# BMS-S09-V00-TemperatureSensors.net
KiCad netlist of a schematic drawn in Altium Designer
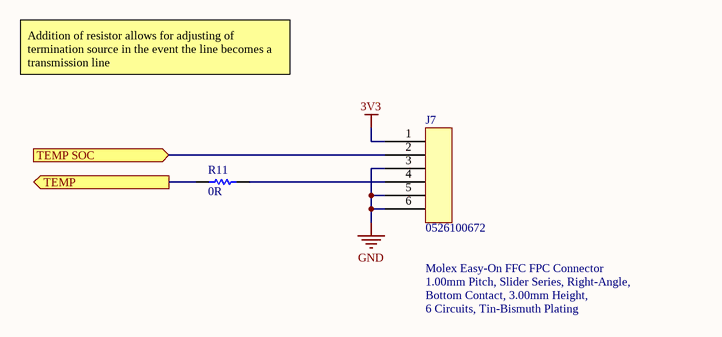
[diagram p0: BMS-S09-V00-TemperatureSensors.SchDoc]

(export (version "E")
  (design (tool "Eeschema 10.0.6"))
  (components
    (comp (ref "J7")
      (value "0526100672")
      (footprint "526100672")
      (libsource (lib "FFCConnectors") (part "6PinMOLEX"))
    )
    (comp (ref "R11")
      (value "0R")
      (footprint "Res_ThinFilm_0603")
      (description "Resistor, SMD, 0R, 0.1W, 5%, 0603")
      (libsource (lib "StandardResistors") (part "0R 5% 0603"))
    )
  )
  (nets
    (net (code "1") (name "/TEMP") (class "Default")
      (node (ref "R11") (pin "1") (pinfunction "1_1") (pintype "passive"))
    )
    (net (code "2") (name "/TEMP SOC") (class "Default")
      (node (ref "J7") (pin "2") (pinfunction "1_2") (pintype "passive"))
    )
    (net (code "3") (name "3V3") (class "Default")
      (node (ref "J7") (pin "1") (pinfunction "0_1") (pintype "passive"))
    )
    (net (code "4") (name "GND") (class "Default")
      (node (ref "J7") (pin "3") (pinfunction "2_3") (pintype "passive"))
      (node (ref "J7") (pin "5") (pinfunction "4_5") (pintype "passive"))
      (node (ref "J7") (pin "6") (pinfunction "5_6") (pintype "passive"))
    )
    (net (code "5") (name "Net-(J7-3)") (class "Default")
      (node (ref "J7") (pin "4") (pinfunction "3_4") (pintype "passive"))
      (node (ref "R11") (pin "2") (pinfunction "2_2") (pintype "passive"))
    )
  )
)
